# head_procesing.net
KiCad netlist of a schematic drawn in EAGLE
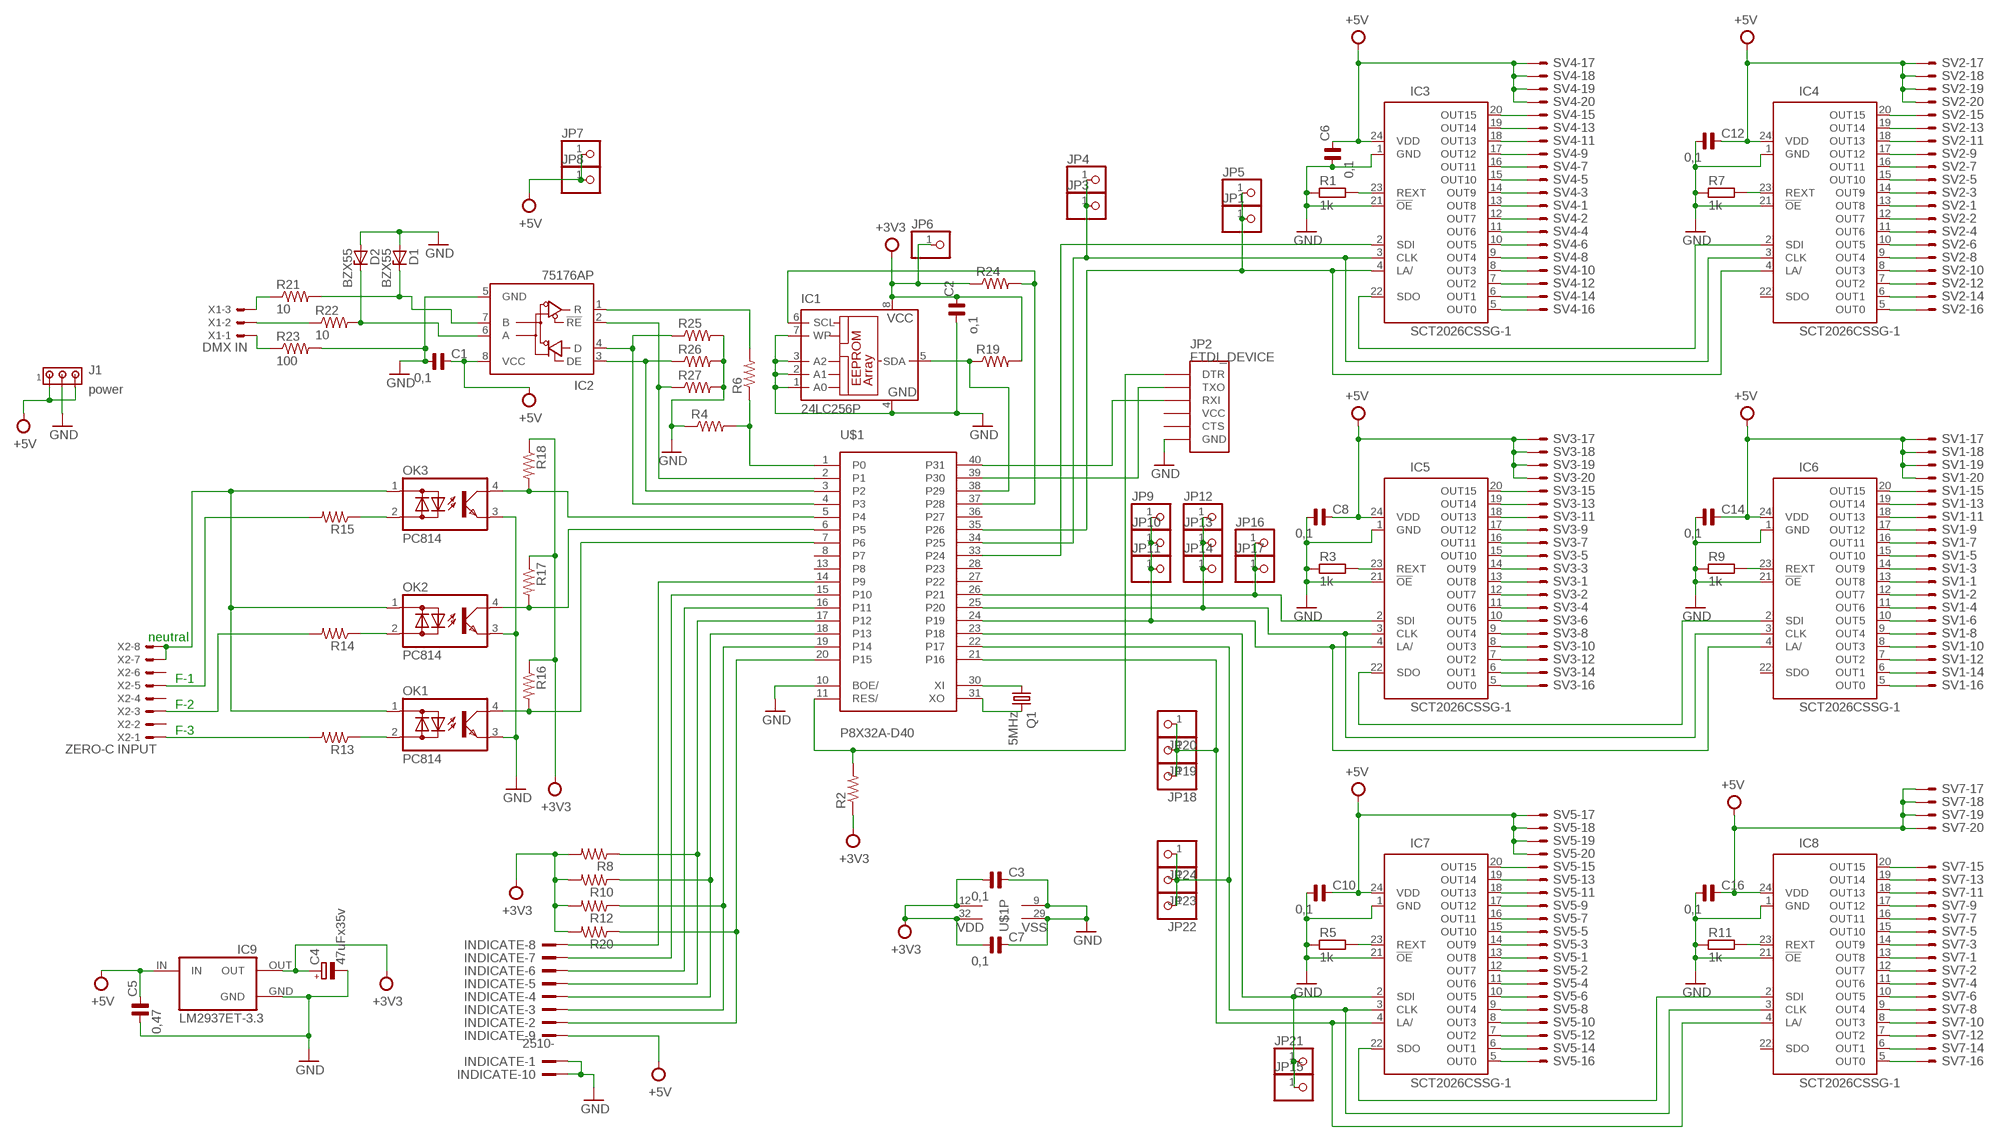
[diagram p0: schematic, sheet 1]

(export (version "E")
  (design (tool "Eeschema 10.0.6"))
  (components
    (comp (ref "C1")
      (value "0,1")
      (footprint "eagle-import:C5,0-7,5X3,5")
      (libsource (lib "eagle-import") (part "C-NP-5,0-7,5X3,5"))
    )
    (comp (ref "C2")
      (value "o,1")
      (footprint "eagle-import:C5,0-7,5X3,5")
      (libsource (lib "eagle-import") (part "C-NP-5,0-7,5X3,5"))
    )
    (comp (ref "C3")
      (value "0,1")
      (footprint "eagle-import:C5,0-7,5X3,5")
      (libsource (lib "eagle-import") (part "C-NP-5,0-7,5X3,5"))
    )
    (comp (ref "C4")
      (value "47uFx35v")
      (footprint "eagle-import:E2-5")
      (libsource (lib "eagle-import") (part "CPOL-EUE2-5"))
    )
    (comp (ref "C5")
      (value "0,47")
      (footprint "eagle-import:C5,0-7,5X3,5")
      (libsource (lib "eagle-import") (part "C-NP-5,0-7,5X3,5"))
    )
    (comp (ref "C6")
      (value "0,1")
      (footprint "eagle-import:C-0805")
      (libsource (lib "eagle-import") (part "C-NP-SMD-0805"))
    )
    (comp (ref "C7")
      (value "0,1")
      (footprint "eagle-import:C5,0-7,5X3,5")
      (libsource (lib "eagle-import") (part "C-NP-5,0-7,5X3,5"))
    )
    (comp (ref "C8")
      (value "0,1")
      (footprint "eagle-import:C-0805")
      (libsource (lib "eagle-import") (part "C-NP-SMD-0805"))
    )
    (comp (ref "C10")
      (value "0,1")
      (footprint "eagle-import:C-0805")
      (libsource (lib "eagle-import") (part "C-NP-SMD-0805"))
    )
    (comp (ref "C12")
      (value "0,1")
      (footprint "eagle-import:C-0805")
      (libsource (lib "eagle-import") (part "C-NP-SMD-0805"))
    )
    (comp (ref "C14")
      (value "0,1")
      (footprint "eagle-import:C-0805")
      (libsource (lib "eagle-import") (part "C-NP-SMD-0805"))
    )
    (comp (ref "C16")
      (value "0,1")
      (footprint "eagle-import:C-0805")
      (libsource (lib "eagle-import") (part "C-NP-SMD-0805"))
    )
    (comp (ref "D1")
      (value "BZX55")
      (footprint "eagle-import:DO35Z10")
      (libsource (lib "eagle-import") (part "BZX55"))
    )
    (comp (ref "D2")
      (value "BZX55")
      (footprint "eagle-import:DO35Z10")
      (libsource (lib "eagle-import") (part "BZX55"))
    )
    (comp (ref "IC1")
      (value "24LC256P")
      (footprint "eagle-import:DIL8")
      (libsource (lib "eagle-import") (part "24PLC256"))
    )
    (comp (ref "IC2")
      (value "75176AP")
      (footprint "eagle-import:DIL08")
      (libsource (lib "eagle-import") (part "75176AP"))
    )
    (comp (ref "IC3")
      (value "SCT2026CSSG-1")
      (footprint "eagle-import:SSOP24")
      (libsource (lib "eagle-import") (part "SCT2026CSSG-1"))
    )
    (comp (ref "IC4")
      (value "SCT2026CSSG-1")
      (footprint "eagle-import:SSOP24")
      (libsource (lib "eagle-import") (part "SCT2026CSSG-1"))
    )
    (comp (ref "IC5")
      (value "SCT2026CSSG-1")
      (footprint "eagle-import:SSOP24")
      (libsource (lib "eagle-import") (part "SCT2026CSSG-1"))
    )
    (comp (ref "IC6")
      (value "SCT2026CSSG-1")
      (footprint "eagle-import:SSOP24")
      (libsource (lib "eagle-import") (part "SCT2026CSSG-1"))
    )
    (comp (ref "IC7")
      (value "SCT2026CSSG-1")
      (footprint "eagle-import:SSOP24")
      (libsource (lib "eagle-import") (part "SCT2026CSSG-1"))
    )
    (comp (ref "IC8")
      (value "SCT2026CSSG-1")
      (footprint "eagle-import:SSOP24")
      (libsource (lib "eagle-import") (part "SCT2026CSSG-1"))
    )
    (comp (ref "IC9")
      (value "LM2937ET-3.3")
      (footprint "eagle-import:TO220(V)")
      (libsource (lib "eagle-import") (part "LM2937ET-3.3"))
    )
    (comp (ref "INDICATE")
      (value "2510-")
      (footprint "eagle-import:PAK100_2500-10")
      (libsource (lib "eagle-import") (part "2510-"))
    )
    (comp (ref "J1")
      (value "power")
      (footprint "eagle-import:350429-1")
      (libsource (lib "eagle-import") (part "350429-1"))
    )
    (comp (ref "JP1")
      (value "PINHD-1X1")
      (footprint "eagle-import:1X01")
      (libsource (lib "eagle-import") (part "PINHD-1X1"))
    )
    (comp (ref "JP2")
      (value "FTDI_DEVICE")
      (footprint "eagle-import:FTDI_DEVICE_SIDE")
      (libsource (lib "eagle-import") (part "FTDI_DEVICE"))
    )
    (comp (ref "JP3")
      (value "PINHD-1X1")
      (footprint "eagle-import:1X01")
      (libsource (lib "eagle-import") (part "PINHD-1X1"))
    )
    (comp (ref "JP4")
      (value "PINHD-1X1")
      (footprint "eagle-import:1X01")
      (libsource (lib "eagle-import") (part "PINHD-1X1"))
    )
    (comp (ref "JP5")
      (value "PINHD-1X1")
      (footprint "eagle-import:1X01")
      (libsource (lib "eagle-import") (part "PINHD-1X1"))
    )
    (comp (ref "JP6")
      (value "PINHD-1X1")
      (footprint "eagle-import:1X01")
      (libsource (lib "eagle-import") (part "PINHD-1X1"))
    )
    (comp (ref "JP7")
      (value "PINHD-1X1")
      (footprint "eagle-import:1X01")
      (libsource (lib "eagle-import") (part "PINHD-1X1"))
    )
    (comp (ref "JP8")
      (value "PINHD-1X1")
      (footprint "eagle-import:1X01")
      (libsource (lib "eagle-import") (part "PINHD-1X1"))
    )
    (comp (ref "JP9")
      (value "PINHD-1X1")
      (footprint "eagle-import:1X01")
      (libsource (lib "eagle-import") (part "PINHD-1X1"))
    )
    (comp (ref "JP10")
      (value "PINHD-1X1")
      (footprint "eagle-import:1X01")
      (libsource (lib "eagle-import") (part "PINHD-1X1"))
    )
    (comp (ref "JP11")
      (value "PINHD-1X1")
      (footprint "eagle-import:1X01")
      (libsource (lib "eagle-import") (part "PINHD-1X1"))
    )
    (comp (ref "JP12")
      (value "PINHD-1X1")
      (footprint "eagle-import:1X01")
      (libsource (lib "eagle-import") (part "PINHD-1X1"))
    )
    (comp (ref "JP13")
      (value "PINHD-1X1")
      (footprint "eagle-import:1X01")
      (libsource (lib "eagle-import") (part "PINHD-1X1"))
    )
    (comp (ref "JP14")
      (value "PINHD-1X1")
      (footprint "eagle-import:1X01")
      (libsource (lib "eagle-import") (part "PINHD-1X1"))
    )
    (comp (ref "JP15")
      (value "PINHD-1X1")
      (footprint "eagle-import:1X01")
      (libsource (lib "eagle-import") (part "PINHD-1X1"))
    )
    (comp (ref "JP16")
      (value "PINHD-1X1")
      (footprint "eagle-import:1X01")
      (libsource (lib "eagle-import") (part "PINHD-1X1"))
    )
    (comp (ref "JP17")
      (value "PINHD-1X1")
      (footprint "eagle-import:1X01")
      (libsource (lib "eagle-import") (part "PINHD-1X1"))
    )
    (comp (ref "JP18")
      (value "PINHD-1X1")
      (footprint "eagle-import:1X01")
      (libsource (lib "eagle-import") (part "PINHD-1X1"))
    )
    (comp (ref "JP19")
      (value "PINHD-1X1")
      (footprint "eagle-import:1X01")
      (libsource (lib "eagle-import") (part "PINHD-1X1"))
    )
    (comp (ref "JP20")
      (value "PINHD-1X1")
      (footprint "eagle-import:1X01")
      (libsource (lib "eagle-import") (part "PINHD-1X1"))
    )
    (comp (ref "JP21")
      (value "PINHD-1X1")
      (footprint "eagle-import:1X01")
      (libsource (lib "eagle-import") (part "PINHD-1X1"))
    )
    (comp (ref "JP22")
      (value "PINHD-1X1")
      (footprint "eagle-import:1X01")
      (libsource (lib "eagle-import") (part "PINHD-1X1"))
    )
    (comp (ref "JP23")
      (value "PINHD-1X1")
      (footprint "eagle-import:1X01")
      (libsource (lib "eagle-import") (part "PINHD-1X1"))
    )
    (comp (ref "JP24")
      (value "PINHD-1X1")
      (footprint "eagle-import:1X01")
      (libsource (lib "eagle-import") (part "PINHD-1X1"))
    )
    (comp (ref "OK1")
      (value "PC814")
      (footprint "eagle-import:DIL04")
      (libsource (lib "eagle-import") (part "PC814"))
    )
    (comp (ref "OK2")
      (value "PC814")
      (footprint "eagle-import:DIL04")
      (libsource (lib "eagle-import") (part "PC814"))
    )
    (comp (ref "OK3")
      (value "PC814")
      (footprint "eagle-import:DIL04")
      (libsource (lib "eagle-import") (part "PC814"))
    )
    (comp (ref "Q1")
      (value "5MHz")
      (footprint "eagle-import:HC49U-V")
      (libsource (lib "eagle-import") (part "CRYTALHC49U-V"))
    )
    (comp (ref "R1")
      (value "1k")
      (footprint "eagle-import:RESC2012X70N")
      (libsource (lib "eagle-import") (part "RESISTOR_0805"))
    )
    (comp (ref "R2")
      (value "R-US_0207/10")
      (footprint "eagle-import:0207_10")
      (libsource (lib "eagle-import") (part "R-US_0207/10"))
    )
    (comp (ref "R3")
      (value "1k")
      (footprint "eagle-import:RESC2012X70N")
      (libsource (lib "eagle-import") (part "RESISTOR_0805"))
    )
    (comp (ref "R4")
      (value "R-US_0207/10")
      (footprint "eagle-import:0207_10")
      (libsource (lib "eagle-import") (part "R-US_0207/10"))
    )
    (comp (ref "R5")
      (value "1k")
      (footprint "eagle-import:RESC2012X70N")
      (libsource (lib "eagle-import") (part "RESISTOR_0805"))
    )
    (comp (ref "R6")
      (value "R-US_0207/10")
      (footprint "eagle-import:0207_10")
      (libsource (lib "eagle-import") (part "R-US_0207/10"))
    )
    (comp (ref "R7")
      (value "1k")
      (footprint "eagle-import:RESC2012X70N")
      (libsource (lib "eagle-import") (part "RESISTOR_0805"))
    )
    (comp (ref "R8")
      (value "R-US_0207/10")
      (footprint "eagle-import:0207_10")
      (libsource (lib "eagle-import") (part "R-US_0207/10"))
    )
    (comp (ref "R9")
      (value "1k")
      (footprint "eagle-import:RESC2012X70N")
      (libsource (lib "eagle-import") (part "RESISTOR_0805"))
    )
    (comp (ref "R10")
      (value "R-US_0207/10")
      (footprint "eagle-import:0207_10")
      (libsource (lib "eagle-import") (part "R-US_0207/10"))
    )
    (comp (ref "R11")
      (value "1k")
      (footprint "eagle-import:RESC2012X70N")
      (libsource (lib "eagle-import") (part "RESISTOR_0805"))
    )
    (comp (ref "R12")
      (value "R-US_0207/10")
      (footprint "eagle-import:0207_10")
      (libsource (lib "eagle-import") (part "R-US_0207/10"))
    )
    (comp (ref "R13")
      (value "R-US_0207/10")
      (footprint "eagle-import:0207_10")
      (libsource (lib "eagle-import") (part "R-US_0207/10"))
    )
    (comp (ref "R14")
      (value "R-US_0207/10")
      (footprint "eagle-import:0207_10")
      (libsource (lib "eagle-import") (part "R-US_0207/10"))
    )
    (comp (ref "R15")
      (value "R-US_0207/10")
      (footprint "eagle-import:0207_10")
      (libsource (lib "eagle-import") (part "R-US_0207/10"))
    )
    (comp (ref "R16")
      (value "R-US_0207/10")
      (footprint "eagle-import:0207_10")
      (libsource (lib "eagle-import") (part "R-US_0207/10"))
    )
    (comp (ref "R17")
      (value "R-US_0207/10")
      (footprint "eagle-import:0207_10")
      (libsource (lib "eagle-import") (part "R-US_0207/10"))
    )
    (comp (ref "R18")
      (value "R-US_0207/10")
      (footprint "eagle-import:0207_10")
      (libsource (lib "eagle-import") (part "R-US_0207/10"))
    )
    (comp (ref "R19")
      (value "R-US_0207/10")
      (footprint "eagle-import:0207_10")
      (libsource (lib "eagle-import") (part "R-US_0207/10"))
    )
    (comp (ref "R20")
      (value "R-US_0207/10")
      (footprint "eagle-import:0207_10")
      (libsource (lib "eagle-import") (part "R-US_0207/10"))
    )
    (comp (ref "R21")
      (value "10")
      (footprint "eagle-import:0207_10")
      (libsource (lib "eagle-import") (part "R-US_0207/10"))
    )
    (comp (ref "R22")
      (value "10")
      (footprint "eagle-import:0207_10")
      (libsource (lib "eagle-import") (part "R-US_0207/10"))
    )
    (comp (ref "R23")
      (value "100")
      (footprint "eagle-import:0207_10")
      (libsource (lib "eagle-import") (part "R-US_0207/10"))
    )
    (comp (ref "R24")
      (value "R-US_0207/10")
      (footprint "eagle-import:0207_10")
      (libsource (lib "eagle-import") (part "R-US_0207/10"))
    )
    (comp (ref "R25")
      (value "R-US_0207/10")
      (footprint "eagle-import:0207_10")
      (libsource (lib "eagle-import") (part "R-US_0207/10"))
    )
    (comp (ref "R26")
      (value "R-US_0207/10")
      (footprint "eagle-import:0207_10")
      (libsource (lib "eagle-import") (part "R-US_0207/10"))
    )
    (comp (ref "R27")
      (value "R-US_0207/10")
      (footprint "eagle-import:0207_10")
      (libsource (lib "eagle-import") (part "R-US_0207/10"))
    )
    (comp (ref "SV1")
      (value "ML20E")
      (footprint "eagle-import:ML20")
      (libsource (lib "eagle-import") (part "ML20?E"))
    )
    (comp (ref "SV2")
      (value "ML20E")
      (footprint "eagle-import:ML20")
      (libsource (lib "eagle-import") (part "ML20?E"))
    )
    (comp (ref "SV3")
      (value "ML20E")
      (footprint "eagle-import:ML20")
      (libsource (lib "eagle-import") (part "ML20?E"))
    )
    (comp (ref "SV4")
      (value "ML20E")
      (footprint "eagle-import:ML20")
      (libsource (lib "eagle-import") (part "ML20?E"))
    )
    (comp (ref "SV5")
      (value "ML20E")
      (footprint "eagle-import:ML20")
      (libsource (lib "eagle-import") (part "ML20?E"))
    )
    (comp (ref "SV7")
      (value "ML20E")
      (footprint "eagle-import:ML20")
      (libsource (lib "eagle-import") (part "ML20?E"))
    )
    (comp (ref "U$1")
      (value "P8X32A-D40")
      (footprint "eagle-import:P8X32A-D40")
      (libsource (lib "eagle-import") (part "P8X32A-D40"))
    )
    (comp (ref "X1")
      (value "DMX IN")
      (footprint "eagle-import:70543-03")
      (libsource (lib "eagle-import") (part "C-GRID-03-70543"))
    )
    (comp (ref "X2")
      (value "ZERO-C INPUT")
      (footprint "eagle-import:70543-08")
      (libsource (lib "eagle-import") (part "C-GRID-08-70543"))
    )
  )
  (nets
    (net (code "1") (name "+3V3") (class "Default")
      (node (ref "C2") (pin "2") (pinfunction "2_2") (pintype "passive"))
      (node (ref "C3") (pin "1") (pinfunction "1_1") (pintype "passive"))
      (node (ref "C4") (pin "+") (pinfunction "+_+") (pintype "passive"))
      (node (ref "C7") (pin "1") (pinfunction "1_1") (pintype "passive"))
      (node (ref "IC1") (pin "8") (pinfunction "VCC_8") (pintype "power_in"))
      (node (ref "IC9") (pin "OUT") (pinfunction "OUT_OUT") (pintype "output"))
      (node (ref "JP6") (pin "1") (pinfunction "1_1") (pintype "passive"))
      (node (ref "R10") (pin "2") (pinfunction "2_2") (pintype "passive"))
      (node (ref "R12") (pin "2") (pinfunction "2_2") (pintype "passive"))
      (node (ref "R16") (pin "1") (pinfunction "1_1") (pintype "passive"))
      (node (ref "R17") (pin "1") (pinfunction "1_1") (pintype "passive"))
      (node (ref "R18") (pin "1") (pinfunction "1_1") (pintype "passive"))
      (node (ref "R19") (pin "2") (pinfunction "2_2") (pintype "passive"))
      (node (ref "R2") (pin "1") (pinfunction "1_1") (pintype "passive"))
      (node (ref "R20") (pin "2") (pinfunction "2_2") (pintype "passive"))
      (node (ref "R24") (pin "1") (pinfunction "1_1") (pintype "passive"))
      (node (ref "R8") (pin "2") (pinfunction "2_2") (pintype "passive"))
      (node (ref "U$1") (pin "12") (pinfunction "VDD_12") (pintype "power_in"))
      (node (ref "U$1") (pin "32") (pinfunction "VDD_32") (pintype "power_in"))
    )
    (net (code "2") (name "+5V") (class "Default")
      (node (ref "C1") (pin "2") (pinfunction "2_2") (pintype "passive"))
      (node (ref "C10") (pin "2") (pinfunction "2_2") (pintype "passive"))
      (node (ref "C12") (pin "2") (pinfunction "2_2") (pintype "passive"))
      (node (ref "C14") (pin "2") (pinfunction "2_2") (pintype "passive"))
      (node (ref "C16") (pin "2") (pinfunction "2_2") (pintype "passive"))
      (node (ref "C5") (pin "2") (pinfunction "2_2") (pintype "passive"))
      (node (ref "C6") (pin "2") (pinfunction "2_2") (pintype "passive"))
      (node (ref "C8") (pin "2") (pinfunction "2_2") (pintype "passive"))
      (node (ref "IC2") (pin "8") (pinfunction "VCC_8") (pintype "power_in"))
      (node (ref "IC3") (pin "24") (pinfunction "VDD_24") (pintype "power_in"))
      (node (ref "IC4") (pin "24") (pinfunction "VDD_24") (pintype "power_in"))
      (node (ref "IC5") (pin "24") (pinfunction "VDD_24") (pintype "power_in"))
      (node (ref "IC6") (pin "24") (pinfunction "VDD_24") (pintype "power_in"))
      (node (ref "IC7") (pin "24") (pinfunction "VDD_24") (pintype "power_in"))
      (node (ref "IC8") (pin "24") (pinfunction "VDD_24") (pintype "power_in"))
      (node (ref "IC9") (pin "IN") (pinfunction "IN_IN") (pintype "input"))
      (node (ref "INDICATE") (pin "9") (pinfunction "KL_9") (pintype "passive"))
      (node (ref "J1") (pin "1") (pinfunction "1_1") (pintype "passive"))
      (node (ref "J1") (pin "3") (pinfunction "3_3") (pintype "passive"))
      (node (ref "JP7") (pin "1") (pinfunction "1_1") (pintype "passive"))
      (node (ref "JP8") (pin "1") (pinfunction "1_1") (pintype "passive"))
      (node (ref "SV1") (pin "17") (pinfunction "S_17") (pintype "passive"))
      (node (ref "SV1") (pin "18") (pinfunction "S_18") (pintype "passive"))
      (node (ref "SV1") (pin "19") (pinfunction "S_19") (pintype "passive"))
      (node (ref "SV1") (pin "20") (pinfunction "S_20") (pintype "passive"))
      (node (ref "SV2") (pin "17") (pinfunction "S_17") (pintype "passive"))
      (node (ref "SV2") (pin "18") (pinfunction "S_18") (pintype "passive"))
      (node (ref "SV2") (pin "19") (pinfunction "S_19") (pintype "passive"))
      (node (ref "SV2") (pin "20") (pinfunction "S_20") (pintype "passive"))
      (node (ref "SV3") (pin "17") (pinfunction "S_17") (pintype "passive"))
      (node (ref "SV3") (pin "18") (pinfunction "S_18") (pintype "passive"))
      (node (ref "SV3") (pin "19") (pinfunction "S_19") (pintype "passive"))
      (node (ref "SV3") (pin "20") (pinfunction "S_20") (pintype "passive"))
      (node (ref "SV4") (pin "17") (pinfunction "S_17") (pintype "passive"))
      (node (ref "SV4") (pin "18") (pinfunction "S_18") (pintype "passive"))
      (node (ref "SV4") (pin "19") (pinfunction "S_19") (pintype "passive"))
      (node (ref "SV4") (pin "20") (pinfunction "S_20") (pintype "passive"))
      (node (ref "SV5") (pin "17") (pinfunction "S_17") (pintype "passive"))
      (node (ref "SV5") (pin "18") (pinfunction "S_18") (pintype "passive"))
      (node (ref "SV5") (pin "19") (pinfunction "S_19") (pintype "passive"))
      (node (ref "SV5") (pin "20") (pinfunction "S_20") (pintype "passive"))
      (node (ref "SV7") (pin "17") (pinfunction "S_17") (pintype "passive"))
      (node (ref "SV7") (pin "18") (pinfunction "S_18") (pintype "passive"))
      (node (ref "SV7") (pin "19") (pinfunction "S_19") (pintype "passive"))
      (node (ref "SV7") (pin "20") (pinfunction "S_20") (pintype "passive"))
    )
    (net (code "3") (name "GND") (class "Default")
      (node (ref "C1") (pin "1") (pinfunction "1_1") (pintype "passive"))
      (node (ref "C10") (pin "1") (pinfunction "1_1") (pintype "passive"))
      (node (ref "C12") (pin "1") (pinfunction "1_1") (pintype "passive"))
      (node (ref "C14") (pin "1") (pinfunction "1_1") (pintype "passive"))
      (node (ref "C16") (pin "1") (pinfunction "1_1") (pintype "passive"))
      (node (ref "C2") (pin "1") (pinfunction "1_1") (pintype "passive"))
      (node (ref "C3") (pin "2") (pinfunction "2_2") (pintype "passive"))
      (node (ref "C4") (pin "-") (pinfunction "-_-") (pintype "passive"))
      (node (ref "C5") (pin "1") (pinfunction "1_1") (pintype "passive"))
      (node (ref "C6") (pin "1") (pinfunction "1_1") (pintype "passive"))
      (node (ref "C7") (pin "2") (pinfunction "2_2") (pintype "passive"))
      (node (ref "C8") (pin "1") (pinfunction "1_1") (pintype "passive"))
      (node (ref "D1") (pin "A") (pinfunction "A_A") (pintype "passive"))
      (node (ref "D2") (pin "A") (pinfunction "A_A") (pintype "passive"))
      (node (ref "IC1") (pin "1") (pinfunction "A0_1") (pintype "input"))
      (node (ref "IC1") (pin "2") (pinfunction "A1_2") (pintype "input"))
      (node (ref "IC1") (pin "3") (pinfunction "A2_3") (pintype "input"))
      (node (ref "IC1") (pin "4") (pinfunction "GND_4") (pintype "power_in"))
      (node (ref "IC1") (pin "7") (pinfunction "WP_7") (pintype "input"))
      (node (ref "IC2") (pin "5") (pinfunction "GND_5") (pintype "power_in"))
      (node (ref "IC3") (pin "1") (pinfunction "GND_1") (pintype "power_in"))
      (node (ref "IC3") (pin "21") (pinfunction "~{OE}_21") (pintype "passive"))
      (node (ref "IC4") (pin "1") (pinfunction "GND_1") (pintype "power_in"))
      (node (ref "IC4") (pin "21") (pinfunction "~{OE}_21") (pintype "passive"))
      (node (ref "IC5") (pin "1") (pinfunction "GND_1") (pintype "power_in"))
      (node (ref "IC5") (pin "21") (pinfunction "~{OE}_21") (pintype "passive"))
      (node (ref "IC6") (pin "1") (pinfunction "GND_1") (pintype "power_in"))
      (node (ref "IC6") (pin "21") (pinfunction "~{OE}_21") (pintype "passive"))
      (node (ref "IC7") (pin "1") (pinfunction "GND_1") (pintype "power_in"))
      (node (ref "IC7") (pin "21") (pinfunction "~{OE}_21") (pintype "passive"))
      (node (ref "IC8") (pin "1") (pinfunction "GND_1") (pintype "power_in"))
      (node (ref "IC8") (pin "21") (pinfunction "~{OE}_21") (pintype "passive"))
      (node (ref "IC9") (pin "GND") (pinfunction "GND_GND") (pintype "power_in"))
      (node (ref "INDICATE") (pin "1") (pinfunction "KL_1") (pintype "passive"))
      (node (ref "INDICATE") (pin "10") (pinfunction "KL_10") (pintype "passive"))
      (node (ref "J1") (pin "2") (pinfunction "2_2") (pintype "passive"))
      (node (ref "JP2") (pin "P$6") (pinfunction "GND_P$6") (pintype "bidirectional"))
      (node (ref "OK1") (pin "3") (pinfunction "E_3") (pintype "passive"))
      (node (ref "OK2") (pin "3") (pinfunction "E_3") (pintype "passive"))
      (node (ref "OK3") (pin "3") (pinfunction "E_3") (pintype "passive"))
      (node (ref "R1") (pin "1") (pinfunction "1_1") (pintype "passive"))
      (node (ref "R11") (pin "1") (pinfunction "1_1") (pintype "passive"))
      (node (ref "R23") (pin "2") (pinfunction "2_2") (pintype "passive"))
      (node (ref "R25") (pin "2") (pinfunction "2_2") (pintype "passive"))
      (node (ref "R26") (pin "2") (pinfunction "2_2") (pintype "passive"))
      (node (ref "R27") (pin "2") (pinfunction "2_2") (pintype "passive"))
      (node (ref "R3") (pin "1") (pinfunction "1_1") (pintype "passive"))
      (node (ref "R4") (pin "1") (pinfunction "1_1") (pintype "passive"))
      (node (ref "R5") (pin "1") (pinfunction "1_1") (pintype "passive"))
      (node (ref "R7") (pin "1") (pinfunction "1_1") (pintype "passive"))
      (node (ref "R9") (pin "1") (pinfunction "1_1") (pintype "passive"))
      (node (ref "U$1") (pin "10") (pinfunction "BOE/_10") (pintype "input"))
      (node (ref "U$1") (pin "29") (pinfunction "VSS_29") (pintype "power_in"))
      (node (ref "U$1") (pin "9") (pinfunction "VSS_9") (pintype "power_in"))
    )
    (net (code "4") (name "Net-(IC1-SCL)") (class "Default")
      (node (ref "IC1") (pin "6") (pinfunction "SCL_6") (pintype "input"))
      (node (ref "R24") (pin "2") (pinfunction "2_2") (pintype "passive"))
      (node (ref "U$1") (pin "37") (pinfunction "P28_37") (pintype "bidirectional"))
    )
    (net (code "5") (name "Net-(IC1-SDA)") (class "Default")
      (node (ref "IC1") (pin "5") (pinfunction "SDA_5") (pintype "bidirectional"))
      (node (ref "R19") (pin "1") (pinfunction "1_1") (pintype "passive"))
      (node (ref "U$1") (pin "38") (pinfunction "P29_38") (pintype "bidirectional"))
    )
    (net (code "6") (name "Net-(IC2-A)") (class "Default")
      (node (ref "D2") (pin "C") (pinfunction "C_C") (pintype "passive"))
      (node (ref "IC2") (pin "6") (pinfunction "A_6") (pintype "output"))
      (node (ref "R22") (pin "2") (pinfunction "2_2") (pintype "passive"))
    )
    (net (code "7") (name "Net-(IC2-B)") (class "Default")
      (node (ref "D1") (pin "C") (pinfunction "C_C") (pintype "passive"))
      (node (ref "IC2") (pin "7") (pinfunction "B_7") (pintype "output"))
      (node (ref "R21") (pin "2") (pinfunction "2_2") (pintype "passive"))
    )
    (net (code "8") (name "Net-(IC2-D)") (class "Default")
      (node (ref "IC2") (pin "4") (pinfunction "D_4") (pintype "input"))
      (node (ref "R25") (pin "1") (pinfunction "1_1") (pintype "passive"))
      (node (ref "U$1") (pin "4") (pinfunction "P3_4") (pintype "bidirectional"))
    )
    (net (code "9") (name "Net-(IC2-DE)") (class "Default")
      (node (ref "IC2") (pin "3") (pinfunction "DE_3") (pintype "input"))
      (node (ref "R26") (pin "1") (pinfunction "1_1") (pintype "passive"))
      (node (ref "U$1") (pin "3") (pinfunction "P2_3") (pintype "bidirectional"))
    )
    (net (code "10") (name "Net-(IC2-R)") (class "Default")
      (node (ref "IC2") (pin "1") (pinfunction "R_1") (pintype "input"))
      (node (ref "R6") (pin "2") (pinfunction "2_2") (pintype "passive"))
    )
    (net (code "11") (name "Net-(IC2-~{RE})") (class "Default")
      (node (ref "IC2") (pin "2") (pinfunction "~{RE}_2") (pintype "input"))
      (node (ref "R27") (pin "1") (pinfunction "1_1") (pintype "passive"))
      (node (ref "U$1") (pin "2") (pinfunction "P1_2") (pintype "bidirectional"))
    )
    (net (code "12") (name "Net-(IC3-CLK)") (class "Default")
      (node (ref "IC3") (pin "3") (pinfunction "CLK_3") (pintype "input"))
      (node (ref "IC4") (pin "3") (pinfunction "CLK_3") (pintype "input"))
      (node (ref "JP3") (pin "1") (pinfunction "1_1") (pintype "passive"))
      (node (ref "JP4") (pin "1") (pinfunction "1_1") (pintype "passive"))
      (node (ref "U$1") (pin "34") (pinfunction "P25_34") (pintype "bidirectional"))
    )
    (net (code "13") (name "Net-(IC3-LA{slash})") (class "Default")
      (node (ref "IC3") (pin "4") (pinfunction "LA/_4") (pintype "input"))
      (node (ref "IC4") (pin "4") (pinfunction "LA/_4") (pintype "input"))
      (node (ref "JP1") (pin "1") (pinfunction "1_1") (pintype "passive"))
      (node (ref "JP5") (pin "1") (pinfunction "1_1") (pintype "passive"))
      (node (ref "U$1") (pin "35") (pinfunction "P26_35") (pintype "bidirectional"))
    )
    (net (code "14") (name "Net-(IC3-OUT0)") (class "Default")
      (node (ref "IC3") (pin "5") (pinfunction "OUT0_5") (pintype "output"))
      (node (ref "SV4") (pin "16") (pinfunction "S_16") (pintype "passive"))
    )
    (net (code "15") (name "Net-(IC3-OUT1)") (class "Default")
      (node (ref "IC3") (pin "6") (pinfunction "OUT1_6") (pintype "output"))
      (node (ref "SV4") (pin "14") (pinfunction "S_14") (pintype "passive"))
    )
    (net (code "16") (name "Net-(IC3-OUT2)") (class "Default")
      (node (ref "IC3") (pin "7") (pinfunction "OUT2_7") (pintype "output"))
      (node (ref "SV4") (pin "12") (pinfunction "S_12") (pintype "passive"))
    )
    (net (code "17") (name "Net-(IC3-OUT3)") (class "Default")
      (node (ref "IC3") (pin "8") (pinfunction "OUT3_8") (pintype "output"))
      (node (ref "SV4") (pin "10") (pinfunction "S_10") (pintype "passive"))
    )
    (net (code "18") (name "Net-(IC3-OUT4)") (class "Default")
      (node (ref "IC3") (pin "9") (pinfunction "OUT4_9") (pintype "output"))
      (node (ref "SV4") (pin "8") (pinfunction "S_8") (pintype "passive"))
    )
    (net (code "19") (name "Net-(IC3-OUT5)") (class "Default")
      (node (ref "IC3") (pin "10") (pinfunction "OUT5_10") (pintype "output"))
      (node (ref "SV4") (pin "6") (pinfunction "S_6") (pintype "passive"))
    )
    (net (code "20") (name "Net-(IC3-OUT6)") (class "Default")
      (node (ref "IC3") (pin "11") (pinfunction "OUT6_11") (pintype "output"))
      (node (ref "SV4") (pin "4") (pinfunction "S_4") (pintype "passive"))
    )
    (net (code "21") (name "Net-(IC3-OUT7)") (class "Default")
      (node (ref "IC3") (pin "12") (pinfunction "OUT7_12") (pintype "output"))
      (node (ref "SV4") (pin "2") (pinfunction "S_2") (pintype "passive"))
    )
    (net (code "22") (name "Net-(IC3-OUT8)") (class "Default")
      (node (ref "IC3") (pin "13") (pinfunction "OUT8_13") (pintype "output"))
      (node (ref "SV4") (pin "1") (pinfunction "S_1") (pintype "passive"))
    )
    (net (code "23") (name "Net-(IC3-OUT9)") (class "Default")
      (node (ref "IC3") (pin "14") (pinfunction "OUT9_14") (pintype "output"))
      (node (ref "SV4") (pin "3") (pinfunction "S_3") (pintype "passive"))
    )
    (net (code "24") (name "Net-(IC3-OUT10)") (class "Default")
      (node (ref "IC3") (pin "15") (pinfunction "OUT10_15") (pintype "output"))
      (node (ref "SV4") (pin "5") (pinfunction "S_5") (pintype "passive"))
    )
    (net (code "25") (name "Net-(IC3-OUT11)") (class "Default")
      (node (ref "IC3") (pin "16") (pinfunction "OUT11_16") (pintype "output"))
      (node (ref "SV4") (pin "7") (pinfunction "S_7") (pintype "passive"))
    )
    (net (code "26") (name "Net-(IC3-OUT12)") (class "Default")
      (node (ref "IC3") (pin "17") (pinfunction "OUT12_17") (pintype "output"))
      (node (ref "SV4") (pin "9") (pinfunction "S_9") (pintype "passive"))
    )
    (net (code "27") (name "Net-(IC3-OUT13)") (class "Default")
      (node (ref "IC3") (pin "18") (pinfunction "OUT13_18") (pintype "output"))
      (node (ref "SV4") (pin "11") (pinfunction "S_11") (pintype "passive"))
    )
    (net (code "28") (name "Net-(IC3-OUT14)") (class "Default")
      (node (ref "IC3") (pin "19") (pinfunction "OUT14_19") (pintype "output"))
      (node (ref "SV4") (pin "13") (pinfunction "S_13") (pintype "passive"))
    )
    (net (code "29") (name "Net-(IC3-OUT15)") (class "Default")
      (node (ref "IC3") (pin "20") (pinfunction "OUT15_20") (pintype "output"))
      (node (ref "SV4") (pin "15") (pinfunction "S_15") (pintype "passive"))
    )
    (net (code "30") (name "Net-(IC3-REXT)") (class "Default")
      (node (ref "IC3") (pin "23") (pinfunction "REXT_23") (pintype "passive"))
      (node (ref "R1") (pin "2") (pinfunction "2_2") (pintype "passive"))
    )
    (net (code "31") (name "Net-(IC3-SDI)") (class "Default")
      (node (ref "IC3") (pin "2") (pinfunction "SDI_2") (pintype "input"))
      (node (ref "U$1") (pin "33") (pinfunction "P24_33") (pintype "bidirectional"))
    )
    (net (code "32") (name "Net-(IC3-SDO)") (class "Default")
      (node (ref "IC3") (pin "22") (pinfunction "SDO_22") (pintype "output"))
      (node (ref "IC4") (pin "2") (pinfunction "SDI_2") (pintype "input"))
    )
    (net (code "33") (name "Net-(IC4-OUT0)") (class "Default")
      (node (ref "IC4") (pin "5") (pinfunction "OUT0_5") (pintype "output"))
      (node (ref "SV2") (pin "16") (pinfunction "S_16") (pintype "passive"))
    )
    (net (code "34") (name "Net-(IC4-OUT1)") (class "Default")
      (node (ref "IC4") (pin "6") (pinfunction "OUT1_6") (pintype "output"))
      (node (ref "SV2") (pin "14") (pinfunction "S_14") (pintype "passive"))
    )
    (net (code "35") (name "Net-(IC4-OUT2)") (class "Default")
      (node (ref "IC4") (pin "7") (pinfunction "OUT2_7") (pintype "output"))
      (node (ref "SV2") (pin "12") (pinfunction "S_12") (pintype "passive"))
    )
    (net (code "36") (name "Net-(IC4-OUT3)") (class "Default")
      (node (ref "IC4") (pin "8") (pinfunction "OUT3_8") (pintype "output"))
      (node (ref "SV2") (pin "10") (pinfunction "S_10") (pintype "passive"))
    )
    (net (code "37") (name "Net-(IC4-OUT4)") (class "Default")
      (node (ref "IC4") (pin "9") (pinfunction "OUT4_9") (pintype "output"))
      (node (ref "SV2") (pin "8") (pinfunction "S_8") (pintype "passive"))
    )
    (net (code "38") (name "Net-(IC4-OUT5)") (class "Default")
      (node (ref "IC4") (pin "10") (pinfunction "OUT5_10") (pintype "output"))
      (node (ref "SV2") (pin "6") (pinfunction "S_6") (pintype "passive"))
    )
    (net (code "39") (name "Net-(IC4-OUT6)") (class "Default")
      (node (ref "IC4") (pin "11") (pinfunction "OUT6_11") (pintype "output"))
      (node (ref "SV2") (pin "4") (pinfunction "S_4") (pintype "passive"))
    )
    (net (code "40") (name "Net-(IC4-OUT7)") (class "Default")
      (node (ref "IC4") (pin "12") (pinfunction "OUT7_12") (pintype "output"))
      (node (ref "SV2") (pin "2") (pinfunction "S_2") (pintype "passive"))
    )
    (net (code "41") (name "Net-(IC4-OUT8)") (class "Default")
      (node (ref "IC4") (pin "13") (pinfunction "OUT8_13") (pintype "output"))
      (node (ref "SV2") (pin "1") (pinfunction "S_1") (pintype "passive"))
    )
    (net (code "42") (name "Net-(IC4-OUT9)") (class "Default")
      (node (ref "IC4") (pin "14") (pinfunction "OUT9_14") (pintype "output"))
      (node (ref "SV2") (pin "3") (pinfunction "S_3") (pintype "passive"))
    )
    (net (code "43") (name "Net-(IC4-OUT10)") (class "Default")
      (node (ref "IC4") (pin "15") (pinfunction "OUT10_15") (pintype "output"))
      (node (ref "SV2") (pin "5") (pinfunction "S_5") (pintype "passive"))
    )
    (net (code "44") (name "Net-(IC4-OUT11)") (class "Default")
      (node (ref "IC4") (pin "16") (pinfunction "OUT11_16") (pintype "output"))
      (node (ref "SV2") (pin "7") (pinfunction "S_7") (pintype "passive"))
    )
    (net (code "45") (name "Net-(IC4-OUT12)") (class "Default")
      (node (ref "IC4") (pin "17") (pinfunction "OUT12_17") (pintype "output"))
      (node (ref "SV2") (pin "9") (pinfunction "S_9") (pintype "passive"))
    )
    (net (code "46") (name "Net-(IC4-OUT13)") (class "Default")
      (node (ref "IC4") (pin "18") (pinfunction "OUT13_18") (pintype "output"))
      (node (ref "SV2") (pin "11") (pinfunction "S_11") (pintype "passive"))
    )
    (net (code "47") (name "Net-(IC4-OUT14)") (class "Default")
      (node (ref "IC4") (pin "19") (pinfunction "OUT14_19") (pintype "output"))
      (node (ref "SV2") (pin "13") (pinfunction "S_13") (pintype "passive"))
    )
    (net (code "48") (name "Net-(IC4-OUT15)") (class "Default")
      (node (ref "IC4") (pin "20") (pinfunction "OUT15_20") (pintype "output"))
      (node (ref "SV2") (pin "15") (pinfunction "S_15") (pintype "passive"))
    )
    (net (code "49") (name "Net-(IC4-REXT)") (class "Default")
      (node (ref "IC4") (pin "23") (pinfunction "REXT_23") (pintype "passive"))
      (node (ref "R7") (pin "2") (pinfunction "2_2") (pintype "passive"))
    )
    (net (code "50") (name "Net-(IC5-CLK)") (class "Default")
      (node (ref "IC5") (pin "3") (pinfunction "CLK_3") (pintype "input"))
      (node (ref "IC6") (pin "3") (pinfunction "CLK_3") (pintype "input"))
      (node (ref "JP12") (pin "1") (pinfunction "1_1") (pintype "passive"))
      (node (ref "JP13") (pin "1") (pinfunction "1_1") (pintype "passive"))
      (node (ref "JP14") (pin "1") (pinfunction "1_1") (pintype "passive"))
      (node (ref "U$1") (pin "25") (pinfunction "P20_25") (pintype "bidirectional"))
    )
    (net (code "51") (name "Net-(IC5-LA{slash})") (class "Default")
      (node (ref "IC5") (pin "4") (pinfunction "LA/_4") (pintype "input"))
      (node (ref "IC6") (pin "4") (pinfunction "LA/_4") (pintype "input"))
      (node (ref "JP10") (pin "1") (pinfunction "1_1") (pintype "passive"))
      (node (ref "JP11") (pin "1") (pinfunction "1_1") (pintype "passive"))
      (node (ref "JP9") (pin "1") (pinfunction "1_1") (pintype "passive"))
      (node (ref "U$1") (pin "24") (pinfunction "P19_24") (pintype "bidirectional"))
    )
    (net (code "52") (name "Net-(IC5-OUT0)") (class "Default")
      (node (ref "IC5") (pin "5") (pinfunction "OUT0_5") (pintype "output"))
      (node (ref "SV3") (pin "16") (pinfunction "S_16") (pintype "passive"))
    )
    (net (code "53") (name "Net-(IC5-OUT1)") (class "Default")
      (node (ref "IC5") (pin "6") (pinfunction "OUT1_6") (pintype "output"))
      (node (ref "SV3") (pin "14") (pinfunction "S_14") (pintype "passive"))
    )
    (net (code "54") (name "Net-(IC5-OUT2)") (class "Default")
      (node (ref "IC5") (pin "7") (pinfunction "OUT2_7") (pintype "output"))
      (node (ref "SV3") (pin "12") (pinfunction "S_12") (pintype "passive"))
    )
    (net (code "55") (name "Net-(IC5-OUT3)") (class "Default")
      (node (ref "IC5") (pin "8") (pinfunction "OUT3_8") (pintype "output"))
      (node (ref "SV3") (pin "10") (pinfunction "S_10") (pintype "passive"))
    )
    (net (code "56") (name "Net-(IC5-OUT4)") (class "Default")
      (node (ref "IC5") (pin "9") (pinfunction "OUT4_9") (pintype "output"))
      (node (ref "SV3") (pin "8") (pinfunction "S_8") (pintype "passive"))
    )
    (net (code "57") (name "Net-(IC5-OUT5)") (class "Default")
      (node (ref "IC5") (pin "10") (pinfunction "OUT5_10") (pintype "output"))
      (node (ref "SV3") (pin "6") (pinfunction "S_6") (pintype "passive"))
    )
    (net (code "58") (name "Net-(IC5-OUT6)") (class "Default")
      (node (ref "IC5") (pin "11") (pinfunction "OUT6_11") (pintype "output"))
      (node (ref "SV3") (pin "4") (pinfunction "S_4") (pintype "passive"))
    )
    (net (code "59") (name "Net-(IC5-OUT7)") (class "Default")
      (node (ref "IC5") (pin "12") (pinfunction "OUT7_12") (pintype "output"))
      (node (ref "SV3") (pin "2") (pinfunction "S_2") (pintype "passive"))
    )
    (net (code "60") (name "Net-(IC5-OUT8)") (class "Default")
      (node (ref "IC5") (pin "13") (pinfunction "OUT8_13") (pintype "output"))
      (node (ref "SV3") (pin "1") (pinfunction "S_1") (pintype "passive"))
    )
    (net (code "61") (name "Net-(IC5-OUT9)") (class "Default")
      (node (ref "IC5") (pin "14") (pinfunction "OUT9_14") (pintype "output"))
      (node (ref "SV3") (pin "3") (pinfunction "S_3") (pintype "passive"))
    )
    (net (code "62") (name "Net-(IC5-OUT10)") (class "Default")
      (node (ref "IC5") (pin "15") (pinfunction "OUT10_15") (pintype "output"))
      (node (ref "SV3") (pin "5") (pinfunction "S_5") (pintype "passive"))
    )
    (net (code "63") (name "Net-(IC5-OUT11)") (class "Default")
      (node (ref "IC5") (pin "16") (pinfunction "OUT11_16") (pintype "output"))
      (node (ref "SV3") (pin "7") (pinfunction "S_7") (pintype "passive"))
    )
    (net (code "64") (name "Net-(IC5-OUT12)") (class "Default")
      (node (ref "IC5") (pin "17") (pinfunction "OUT12_17") (pintype "output"))
      (node (ref "SV3") (pin "9") (pinfunction "S_9") (pintype "passive"))
    )
    (net (code "65") (name "Net-(IC5-OUT13)") (class "Default")
      (node (ref "IC5") (pin "18") (pinfunction "OUT13_18") (pintype "output"))
      (node (ref "SV3") (pin "11") (pinfunction "S_11") (pintype "passive"))
    )
    (net (code "66") (name "Net-(IC5-OUT14)") (class "Default")
      (node (ref "IC5") (pin "19") (pinfunction "OUT14_19") (pintype "output"))
      (node (ref "SV3") (pin "13") (pinfunction "S_13") (pintype "passive"))
    )
    (net (code "67") (name "Net-(IC5-OUT15)") (class "Default")
      (node (ref "IC5") (pin "20") (pinfunction "OUT15_20") (pintype "output"))
      (node (ref "SV3") (pin "15") (pinfunction "S_15") (pintype "passive"))
    )
    (net (code "68") (name "Net-(IC5-REXT)") (class "Default")
      (node (ref "IC5") (pin "23") (pinfunction "REXT_23") (pintype "passive"))
      (node (ref "R3") (pin "2") (pinfunction "2_2") (pintype "passive"))
    )
    (net (code "69") (name "Net-(IC5-SDI)") (class "Default")
      (node (ref "IC5") (pin "2") (pinfunction "SDI_2") (pintype "input"))
      (node (ref "JP16") (pin "1") (pinfunction "1_1") (pintype "passive"))
      (node (ref "JP17") (pin "1") (pinfunction "1_1") (pintype "passive"))
      (node (ref "U$1") (pin "26") (pinfunction "P21_26") (pintype "bidirectional"))
    )
    (net (code "70") (name "Net-(IC5-SDO)") (class "Default")
      (node (ref "IC5") (pin "22") (pinfunction "SDO_22") (pintype "output"))
      (node (ref "IC6") (pin "2") (pinfunction "SDI_2") (pintype "input"))
    )
    (net (code "71") (name "Net-(IC6-OUT0)") (class "Default")
      (node (ref "IC6") (pin "5") (pinfunction "OUT0_5") (pintype "output"))
      (node (ref "SV1") (pin "16") (pinfunction "S_16") (pintype "passive"))
    )
    (net (code "72") (name "Net-(IC6-OUT1)") (class "Default")
      (node (ref "IC6") (pin "6") (pinfunction "OUT1_6") (pintype "output"))
      (node (ref "SV1") (pin "14") (pinfunction "S_14") (pintype "passive"))
    )
    (net (code "73") (name "Net-(IC6-OUT2)") (class "Default")
      (node (ref "IC6") (pin "7") (pinfunction "OUT2_7") (pintype "output"))
      (node (ref "SV1") (pin "12") (pinfunction "S_12") (pintype "passive"))
    )
    (net (code "74") (name "Net-(IC6-OUT3)") (class "Default")
      (node (ref "IC6") (pin "8") (pinfunction "OUT3_8") (pintype "output"))
      (node (ref "SV1") (pin "10") (pinfunction "S_10") (pintype "passive"))
    )
    (net (code "75") (name "Net-(IC6-OUT4)") (class "Default")
      (node (ref "IC6") (pin "9") (pinfunction "OUT4_9") (pintype "output"))
      (node (ref "SV1") (pin "8") (pinfunction "S_8") (pintype "passive"))
    )
    (net (code "76") (name "Net-(IC6-OUT5)") (class "Default")
      (node (ref "IC6") (pin "10") (pinfunction "OUT5_10") (pintype "output"))
      (node (ref "SV1") (pin "6") (pinfunction "S_6") (pintype "passive"))
    )
    (net (code "77") (name "Net-(IC6-OUT6)") (class "Default")
      (node (ref "IC6") (pin "11") (pinfunction "OUT6_11") (pintype "output"))
      (node (ref "SV1") (pin "4") (pinfunction "S_4") (pintype "passive"))
    )
    (net (code "78") (name "Net-(IC6-OUT7)") (class "Default")
      (node (ref "IC6") (pin "12") (pinfunction "OUT7_12") (pintype "output"))
      (node (ref "SV1") (pin "2") (pinfunction "S_2") (pintype "passive"))
    )
    (net (code "79") (name "Net-(IC6-OUT8)") (class "Default")
      (node (ref "IC6") (pin "13") (pinfunction "OUT8_13") (pintype "output"))
      (node (ref "SV1") (pin "1") (pinfunction "S_1") (pintype "passive"))
    )
    (net (code "80") (name "Net-(IC6-OUT9)") (class "Default")
      (node (ref "IC6") (pin "14") (pinfunction "OUT9_14") (pintype "output"))
      (node (ref "SV1") (pin "3") (pinfunction "S_3") (pintype "passive"))
    )
    (net (code "81") (name "Net-(IC6-OUT10)") (class "Default")
      (node (ref "IC6") (pin "15") (pinfunction "OUT10_15") (pintype "output"))
      (node (ref "SV1") (pin "5") (pinfunction "S_5") (pintype "passive"))
    )
    (net (code "82") (name "Net-(IC6-OUT11)") (class "Default")
      (node (ref "IC6") (pin "16") (pinfunction "OUT11_16") (pintype "output"))
      (node (ref "SV1") (pin "7") (pinfunction "S_7") (pintype "passive"))
    )
    (net (code "83") (name "Net-(IC6-OUT12)") (class "Default")
      (node (ref "IC6") (pin "17") (pinfunction "OUT12_17") (pintype "output"))
      (node (ref "SV1") (pin "9") (pinfunction "S_9") (pintype "passive"))
    )
    (net (code "84") (name "Net-(IC6-OUT13)") (class "Default")
      (node (ref "IC6") (pin "18") (pinfunction "OUT13_18") (pintype "output"))
      (node (ref "SV1") (pin "11") (pinfunction "S_11") (pintype "passive"))
    )
    (net (code "85") (name "Net-(IC6-OUT14)") (class "Default")
      (node (ref "IC6") (pin "19") (pinfunction "OUT14_19") (pintype "output"))
      (node (ref "SV1") (pin "13") (pinfunction "S_13") (pintype "passive"))
    )
    (net (code "86") (name "Net-(IC6-OUT15)") (class "Default")
      (node (ref "IC6") (pin "20") (pinfunction "OUT15_20") (pintype "output"))
      (node (ref "SV1") (pin "15") (pinfunction "S_15") (pintype "passive"))
    )
    (net (code "87") (name "Net-(IC6-REXT)") (class "Default")
      (node (ref "IC6") (pin "23") (pinfunction "REXT_23") (pintype "passive"))
      (node (ref "R9") (pin "2") (pinfunction "2_2") (pintype "passive"))
    )
    (net (code "88") (name "Net-(IC7-CLK)") (class "Default")
      (node (ref "IC7") (pin "3") (pinfunction "CLK_3") (pintype "input"))
      (node (ref "IC8") (pin "3") (pinfunction "CLK_3") (pintype "input"))
      (node (ref "JP22") (pin "1") (pinfunction "1_1") (pintype "passive"))
      (node (ref "JP23") (pin "1") (pinfunction "1_1") (pintype "passive"))
      (node (ref "JP24") (pin "1") (pinfunction "1_1") (pintype "passive"))
      (node (ref "U$1") (pin "22") (pinfunction "P17_22") (pintype "bidirectional"))
    )
    (net (code "89") (name "Net-(IC7-LA{slash})") (class "Default")
      (node (ref "IC7") (pin "4") (pinfunction "LA/_4") (pintype "input"))
      (node (ref "IC8") (pin "4") (pinfunction "LA/_4") (pintype "input"))
      (node (ref "JP18") (pin "1") (pinfunction "1_1") (pintype "passive"))
      (node (ref "JP19") (pin "1") (pinfunction "1_1") (pintype "passive"))
      (node (ref "JP20") (pin "1") (pinfunction "1_1") (pintype "passive"))
      (node (ref "U$1") (pin "21") (pinfunction "P16_21") (pintype "bidirectional"))
    )
    (net (code "90") (name "Net-(IC7-OUT0)") (class "Default")
      (node (ref "IC7") (pin "5") (pinfunction "OUT0_5") (pintype "output"))
      (node (ref "SV5") (pin "16") (pinfunction "S_16") (pintype "passive"))
    )
    (net (code "91") (name "Net-(IC7-OUT1)") (class "Default")
      (node (ref "IC7") (pin "6") (pinfunction "OUT1_6") (pintype "output"))
      (node (ref "SV5") (pin "14") (pinfunction "S_14") (pintype "passive"))
    )
    (net (code "92") (name "Net-(IC7-OUT2)") (class "Default")
      (node (ref "IC7") (pin "7") (pinfunction "OUT2_7") (pintype "output"))
      (node (ref "SV5") (pin "12") (pinfunction "S_12") (pintype "passive"))
    )
    (net (code "93") (name "Net-(IC7-OUT3)") (class "Default")
      (node (ref "IC7") (pin "8") (pinfunction "OUT3_8") (pintype "output"))
      (node (ref "SV5") (pin "10") (pinfunction "S_10") (pintype "passive"))
    )
    (net (code "94") (name "Net-(IC7-OUT4)") (class "Default")
      (node (ref "IC7") (pin "9") (pinfunction "OUT4_9") (pintype "output"))
      (node (ref "SV5") (pin "8") (pinfunction "S_8") (pintype "passive"))
    )
    (net (code "95") (name "Net-(IC7-OUT5)") (class "Default")
      (node (ref "IC7") (pin "10") (pinfunction "OUT5_10") (pintype "output"))
      (node (ref "SV5") (pin "6") (pinfunction "S_6") (pintype "passive"))
    )
    (net (code "96") (name "Net-(IC7-OUT6)") (class "Default")
      (node (ref "IC7") (pin "11") (pinfunction "OUT6_11") (pintype "output"))
      (node (ref "SV5") (pin "4") (pinfunction "S_4") (pintype "passive"))
    )
    (net (code "97") (name "Net-(IC7-OUT7)") (class "Default")
      (node (ref "IC7") (pin "12") (pinfunction "OUT7_12") (pintype "output"))
      (node (ref "SV5") (pin "2") (pinfunction "S_2") (pintype "passive"))
    )
    (net (code "98") (name "Net-(IC7-OUT8)") (class "Default")
      (node (ref "IC7") (pin "13") (pinfunction "OUT8_13") (pintype "output"))
      (node (ref "SV5") (pin "1") (pinfunction "S_1") (pintype "passive"))
    )
    (net (code "99") (name "Net-(IC7-OUT9)") (class "Default")
      (node (ref "IC7") (pin "14") (pinfunction "OUT9_14") (pintype "output"))
      (node (ref "SV5") (pin "3") (pinfunction "S_3") (pintype "passive"))
    )
    (net (code "100") (name "Net-(IC7-OUT10)") (class "Default")
      (node (ref "IC7") (pin "15") (pinfunction "OUT10_15") (pintype "output"))
      (node (ref "SV5") (pin "5") (pinfunction "S_5") (pintype "passive"))
    )
    (net (code "101") (name "Net-(IC7-OUT11)") (class "Default")
      (node (ref "IC7") (pin "16") (pinfunction "OUT11_16") (pintype "output"))
      (node (ref "SV5") (pin "7") (pinfunction "S_7") (pintype "passive"))
    )
    (net (code "102") (name "Net-(IC7-OUT12)") (class "Default")
      (node (ref "IC7") (pin "17") (pinfunction "OUT12_17") (pintype "output"))
      (node (ref "SV5") (pin "9") (pinfunction "S_9") (pintype "passive"))
    )
    (net (code "103") (name "Net-(IC7-OUT13)") (class "Default")
      (node (ref "IC7") (pin "18") (pinfunction "OUT13_18") (pintype "output"))
      (node (ref "SV5") (pin "11") (pinfunction "S_11") (pintype "passive"))
    )
    (net (code "104") (name "Net-(IC7-OUT14)") (class "Default")
      (node (ref "IC7") (pin "19") (pinfunction "OUT14_19") (pintype "output"))
      (node (ref "SV5") (pin "13") (pinfunction "S_13") (pintype "passive"))
    )
    (net (code "105") (name "Net-(IC7-OUT15)") (class "Default")
      (node (ref "IC7") (pin "20") (pinfunction "OUT15_20") (pintype "output"))
      (node (ref "SV5") (pin "15") (pinfunction "S_15") (pintype "passive"))
    )
    (net (code "106") (name "Net-(IC7-REXT)") (class "Default")
      (node (ref "IC7") (pin "23") (pinfunction "REXT_23") (pintype "passive"))
      (node (ref "R5") (pin "2") (pinfunction "2_2") (pintype "passive"))
    )
    (net (code "107") (name "Net-(IC7-SDI)") (class "Default")
      (node (ref "IC7") (pin "2") (pinfunction "SDI_2") (pintype "input"))
      (node (ref "JP15") (pin "1") (pinfunction "1_1") (pintype "passive"))
      (node (ref "JP21") (pin "1") (pinfunction "1_1") (pintype "passive"))
      (node (ref "U$1") (pin "23") (pinfunction "P18_23") (pintype "bidirectional"))
    )
    (net (code "108") (name "Net-(IC7-SDO)") (class "Default")
      (node (ref "IC7") (pin "22") (pinfunction "SDO_22") (pintype "output"))
      (node (ref "IC8") (pin "2") (pinfunction "SDI_2") (pintype "input"))
    )
    (net (code "109") (name "Net-(IC8-OUT0)") (class "Default")
      (node (ref "IC8") (pin "5") (pinfunction "OUT0_5") (pintype "output"))
      (node (ref "SV7") (pin "16") (pinfunction "S_16") (pintype "passive"))
    )
    (net (code "110") (name "Net-(IC8-OUT1)") (class "Default")
      (node (ref "IC8") (pin "6") (pinfunction "OUT1_6") (pintype "output"))
      (node (ref "SV7") (pin "14") (pinfunction "S_14") (pintype "passive"))
    )
    (net (code "111") (name "Net-(IC8-OUT2)") (class "Default")
      (node (ref "IC8") (pin "7") (pinfunction "OUT2_7") (pintype "output"))
      (node (ref "SV7") (pin "12") (pinfunction "S_12") (pintype "passive"))
    )
    (net (code "112") (name "Net-(IC8-OUT3)") (class "Default")
      (node (ref "IC8") (pin "8") (pinfunction "OUT3_8") (pintype "output"))
      (node (ref "SV7") (pin "10") (pinfunction "S_10") (pintype "passive"))
    )
    (net (code "113") (name "Net-(IC8-OUT4)") (class "Default")
      (node (ref "IC8") (pin "9") (pinfunction "OUT4_9") (pintype "output"))
      (node (ref "SV7") (pin "8") (pinfunction "S_8") (pintype "passive"))
    )
    (net (code "114") (name "Net-(IC8-OUT5)") (class "Default")
      (node (ref "IC8") (pin "10") (pinfunction "OUT5_10") (pintype "output"))
      (node (ref "SV7") (pin "6") (pinfunction "S_6") (pintype "passive"))
    )
    (net (code "115") (name "Net-(IC8-OUT6)") (class "Default")
      (node (ref "IC8") (pin "11") (pinfunction "OUT6_11") (pintype "output"))
      (node (ref "SV7") (pin "4") (pinfunction "S_4") (pintype "passive"))
    )
    (net (code "116") (name "Net-(IC8-OUT7)") (class "Default")
      (node (ref "IC8") (pin "12") (pinfunction "OUT7_12") (pintype "output"))
      (node (ref "SV7") (pin "2") (pinfunction "S_2") (pintype "passive"))
    )
    (net (code "117") (name "Net-(IC8-OUT8)") (class "Default")
      (node (ref "IC8") (pin "13") (pinfunction "OUT8_13") (pintype "output"))
      (node (ref "SV7") (pin "1") (pinfunction "S_1") (pintype "passive"))
    )
    (net (code "118") (name "Net-(IC8-OUT9)") (class "Default")
      (node (ref "IC8") (pin "14") (pinfunction "OUT9_14") (pintype "output"))
      (node (ref "SV7") (pin "3") (pinfunction "S_3") (pintype "passive"))
    )
    (net (code "119") (name "Net-(IC8-OUT10)") (class "Default")
      (node (ref "IC8") (pin "15") (pinfunction "OUT10_15") (pintype "output"))
      (node (ref "SV7") (pin "5") (pinfunction "S_5") (pintype "passive"))
    )
    (net (code "120") (name "Net-(IC8-OUT11)") (class "Default")
      (node (ref "IC8") (pin "16") (pinfunction "OUT11_16") (pintype "output"))
      (node (ref "SV7") (pin "7") (pinfunction "S_7") (pintype "passive"))
    )
    (net (code "121") (name "Net-(IC8-OUT12)") (class "Default")
      (node (ref "IC8") (pin "17") (pinfunction "OUT12_17") (pintype "output"))
      (node (ref "SV7") (pin "9") (pinfunction "S_9") (pintype "passive"))
    )
    (net (code "122") (name "Net-(IC8-OUT13)") (class "Default")
      (node (ref "IC8") (pin "18") (pinfunction "OUT13_18") (pintype "output"))
      (node (ref "SV7") (pin "11") (pinfunction "S_11") (pintype "passive"))
    )
    (net (code "123") (name "Net-(IC8-OUT14)") (class "Default")
      (node (ref "IC8") (pin "19") (pinfunction "OUT14_19") (pintype "output"))
      (node (ref "SV7") (pin "13") (pinfunction "S_13") (pintype "passive"))
    )
    (net (code "124") (name "Net-(IC8-OUT15)") (class "Default")
      (node (ref "IC8") (pin "20") (pinfunction "OUT15_20") (pintype "output"))
      (node (ref "SV7") (pin "15") (pinfunction "S_15") (pintype "passive"))
    )
    (net (code "125") (name "Net-(IC8-REXT)") (class "Default")
      (node (ref "IC8") (pin "23") (pinfunction "REXT_23") (pintype "passive"))
      (node (ref "R11") (pin "2") (pinfunction "2_2") (pintype "passive"))
    )
    (net (code "126") (name "Net-(INDICATEC-KL)") (class "Default")
      (node (ref "INDICATE") (pin "2") (pinfunction "KL_2") (pintype "passive"))
      (node (ref "R20") (pin "1") (pinfunction "1_1") (pintype "passive"))
      (node (ref "U$1") (pin "20") (pinfunction "P15_20") (pintype "bidirectional"))
    )
    (net (code "127") (name "Net-(INDICATED-KL)") (class "Default")
      (node (ref "INDICATE") (pin "3") (pinfunction "KL_3") (pintype "passive"))
      (node (ref "R12") (pin "1") (pinfunction "1_1") (pintype "passive"))
      (node (ref "U$1") (pin "19") (pinfunction "P14_19") (pintype "bidirectional"))
    )
    (net (code "128") (name "Net-(INDICATEE-KL)") (class "Default")
      (node (ref "INDICATE") (pin "4") (pinfunction "KL_4") (pintype "passive"))
      (node (ref "R10") (pin "1") (pinfunction "1_1") (pintype "passive"))
      (node (ref "U$1") (pin "18") (pinfunction "P13_18") (pintype "bidirectional"))
    )
    (net (code "129") (name "Net-(INDICATEF-KL)") (class "Default")
      (node (ref "INDICATE") (pin "5") (pinfunction "KL_5") (pintype "passive"))
      (node (ref "R8") (pin "1") (pinfunction "1_1") (pintype "passive"))
      (node (ref "U$1") (pin "17") (pinfunction "P12_17") (pintype "bidirectional"))
    )
    (net (code "130") (name "Net-(INDICATEG-KL)") (class "Default")
      (node (ref "INDICATE") (pin "6") (pinfunction "KL_6") (pintype "passive"))
      (node (ref "U$1") (pin "16") (pinfunction "P11_16") (pintype "bidirectional"))
    )
    (net (code "131") (name "Net-(INDICATEH-KL)") (class "Default")
      (node (ref "INDICATE") (pin "7") (pinfunction "KL_7") (pintype "passive"))
      (node (ref "U$1") (pin "15") (pinfunction "P10_15") (pintype "bidirectional"))
    )
    (net (code "132") (name "Net-(INDICATEI-KL)") (class "Default")
      (node (ref "INDICATE") (pin "8") (pinfunction "KL_8") (pintype "passive"))
      (node (ref "U$1") (pin "14") (pinfunction "P9_14") (pintype "bidirectional"))
    )
    (net (code "133") (name "Net-(JP2-DTR)") (class "Default")
      (node (ref "JP2") (pin "P$1") (pinfunction "DTR_P$1") (pintype "bidirectional"))
      (node (ref "R2") (pin "2") (pinfunction "2_2") (pintype "passive"))
      (node (ref "U$1") (pin "11") (pinfunction "RES/_11") (pintype "bidirectional"))
    )
    (net (code "134") (name "Net-(JP2-RXI)") (class "Default")
      (node (ref "JP2") (pin "P$3") (pinfunction "RXI_P$3") (pintype "bidirectional"))
      (node (ref "U$1") (pin "40") (pinfunction "P31_40") (pintype "bidirectional"))
    )
    (net (code "135") (name "Net-(JP2-TXO)") (class "Default")
      (node (ref "JP2") (pin "P$2") (pinfunction "TXO_P$2") (pintype "bidirectional"))
      (node (ref "U$1") (pin "39") (pinfunction "P30_39") (pintype "bidirectional"))
    )
    (net (code "136") (name "Net-(OK1-AC1)") (class "Default")
      (node (ref "OK1") (pin "1") (pinfunction "AC1_1") (pintype "passive"))
      (node (ref "OK2") (pin "1") (pinfunction "AC1_1") (pintype "passive"))
      (node (ref "OK3") (pin "1") (pinfunction "AC1_1") (pintype "passive"))
      (node (ref "X2") (pin "7") (pinfunction "S_7") (pintype "passive"))
      (node (ref "X2") (pin "8") (pinfunction "S_8") (pintype "passive"))
    )
    (net (code "137") (name "Net-(OK1-AC2)") (class "Default")
      (node (ref "OK1") (pin "2") (pinfunction "AC2_2") (pintype "passive"))
      (node (ref "R13") (pin "1") (pinfunction "1_1") (pintype "passive"))
    )
    (net (code "138") (name "Net-(OK1-C)") (class "Default")
      (node (ref "OK1") (pin "4") (pinfunction "C_4") (pintype "passive"))
      (node (ref "R16") (pin "2") (pinfunction "2_2") (pintype "passive"))
      (node (ref "U$1") (pin "7") (pinfunction "P6_7") (pintype "bidirectional"))
    )
    (net (code "139") (name "Net-(OK2-AC2)") (class "Default")
      (node (ref "OK2") (pin "2") (pinfunction "AC2_2") (pintype "passive"))
      (node (ref "R14") (pin "1") (pinfunction "1_1") (pintype "passive"))
    )
    (net (code "140") (name "Net-(OK2-C)") (class "Default")
      (node (ref "OK2") (pin "4") (pinfunction "C_4") (pintype "passive"))
      (node (ref "R17") (pin "2") (pinfunction "2_2") (pintype "passive"))
      (node (ref "U$1") (pin "6") (pinfunction "P5_6") (pintype "bidirectional"))
    )
    (net (code "141") (name "Net-(OK3-AC2)") (class "Default")
      (node (ref "OK3") (pin "2") (pinfunction "AC2_2") (pintype "passive"))
      (node (ref "R15") (pin "1") (pinfunction "1_1") (pintype "passive"))
    )
    (net (code "142") (name "Net-(OK3-C)") (class "Default")
      (node (ref "OK3") (pin "4") (pinfunction "C_4") (pintype "passive"))
      (node (ref "R18") (pin "2") (pinfunction "2_2") (pintype "passive"))
      (node (ref "U$1") (pin "5") (pinfunction "P4_5") (pintype "bidirectional"))
    )
    (net (code "143") (name "Net-(U$1B-P0)") (class "Default")
      (node (ref "R4") (pin "2") (pinfunction "2_2") (pintype "passive"))
      (node (ref "R6") (pin "1") (pinfunction "1_1") (pintype "passive"))
      (node (ref "U$1") (pin "1") (pinfunction "P0_1") (pintype "bidirectional"))
    )
    (net (code "144") (name "Net-(U$1B-XI)") (class "Default")
      (node (ref "Q1") (pin "1") (pinfunction "1_1") (pintype "passive"))
      (node (ref "U$1") (pin "30") (pinfunction "XI_30") (pintype "input"))
    )
    (net (code "145") (name "Net-(U$1B-XO)") (class "Default")
      (node (ref "Q1") (pin "2") (pinfunction "2_2") (pintype "passive"))
      (node (ref "U$1") (pin "31") (pinfunction "XO_31") (pintype "output"))
    )
    (net (code "146") (name "Net-(X1A-S)") (class "Default")
      (node (ref "R23") (pin "1") (pinfunction "1_1") (pintype "passive"))
      (node (ref "X1") (pin "1") (pinfunction "S_1") (pintype "passive"))
    )
    (net (code "147") (name "Net-(X1B-S)") (class "Default")
      (node (ref "R22") (pin "1") (pinfunction "1_1") (pintype "passive"))
      (node (ref "X1") (pin "2") (pinfunction "S_2") (pintype "passive"))
    )
    (net (code "148") (name "Net-(X1C-S)") (class "Default")
      (node (ref "R21") (pin "1") (pinfunction "1_1") (pintype "passive"))
      (node (ref "X1") (pin "3") (pinfunction "S_3") (pintype "passive"))
    )
    (net (code "149") (name "Net-(X2A-S)") (class "Default")
      (node (ref "R13") (pin "2") (pinfunction "2_2") (pintype "passive"))
      (node (ref "X2") (pin "1") (pinfunction "S_1") (pintype "passive"))
    )
    (net (code "150") (name "Net-(X2C-S)") (class "Default")
      (node (ref "R14") (pin "2") (pinfunction "2_2") (pintype "passive"))
      (node (ref "X2") (pin "3") (pinfunction "S_3") (pintype "passive"))
    )
    (net (code "151") (name "Net-(X2E-S)") (class "Default")
      (node (ref "R15") (pin "2") (pinfunction "2_2") (pintype "passive"))
      (node (ref "X2") (pin "5") (pinfunction "S_5") (pintype "passive"))
    )
    (net (code "152") (name "unconnected-(IC4-SDO-Pad22)") (class "Default")
      (node (ref "IC4") (pin "22") (pinfunction "SDO_22") (pintype "output"))
    )
    (net (code "153") (name "unconnected-(IC6-SDO-Pad22)") (class "Default")
      (node (ref "IC6") (pin "22") (pinfunction "SDO_22") (pintype "output"))
    )
    (net (code "154") (name "unconnected-(IC8-SDO-Pad22)") (class "Default")
      (node (ref "IC8") (pin "22") (pinfunction "SDO_22") (pintype "output"))
    )
    (net (code "155") (name "unconnected-(JP2-CTS-PadP$5)") (class "Default")
      (node (ref "JP2") (pin "P$5") (pinfunction "CTS_P$5") (pintype "bidirectional"))
    )
    (net (code "156") (name "unconnected-(JP2-VCC-PadP$4)") (class "Default")
      (node (ref "JP2") (pin "P$4") (pinfunction "VCC_P$4") (pintype "bidirectional"))
    )
    (net (code "157") (name "unconnected-(U$1B-P7-Pad8)") (class "Default")
      (node (ref "U$1") (pin "8") (pinfunction "P7_8") (pintype "bidirectional"))
    )
    (net (code "158") (name "unconnected-(U$1B-P8-Pad13)") (class "Default")
      (node (ref "U$1") (pin "13") (pinfunction "P8_13") (pintype "bidirectional"))
    )
    (net (code "159") (name "unconnected-(U$1B-P22-Pad27)") (class "Default")
      (node (ref "U$1") (pin "27") (pinfunction "P22_27") (pintype "bidirectional"))
    )
    (net (code "160") (name "unconnected-(U$1B-P23-Pad28)") (class "Default")
      (node (ref "U$1") (pin "28") (pinfunction "P23_28") (pintype "bidirectional"))
    )
    (net (code "161") (name "unconnected-(U$1B-P27-Pad36)") (class "Default")
      (node (ref "U$1") (pin "36") (pinfunction "P27_36") (pintype "bidirectional"))
    )
    (net (code "162") (name "unconnected-(X2B-S-Pad2)") (class "Default")
      (node (ref "X2") (pin "2") (pinfunction "S_2") (pintype "passive"))
    )
    (net (code "163") (name "unconnected-(X2D-S-Pad4)") (class "Default")
      (node (ref "X2") (pin "4") (pinfunction "S_4") (pintype "passive"))
    )
    (net (code "164") (name "unconnected-(X2F-S-Pad6)") (class "Default")
      (node (ref "X2") (pin "6") (pinfunction "S_6") (pintype "passive"))
    )
  )
)
